# a314-q_d-vcf.net
KiCad netlist of a schematic drawn in EAGLE
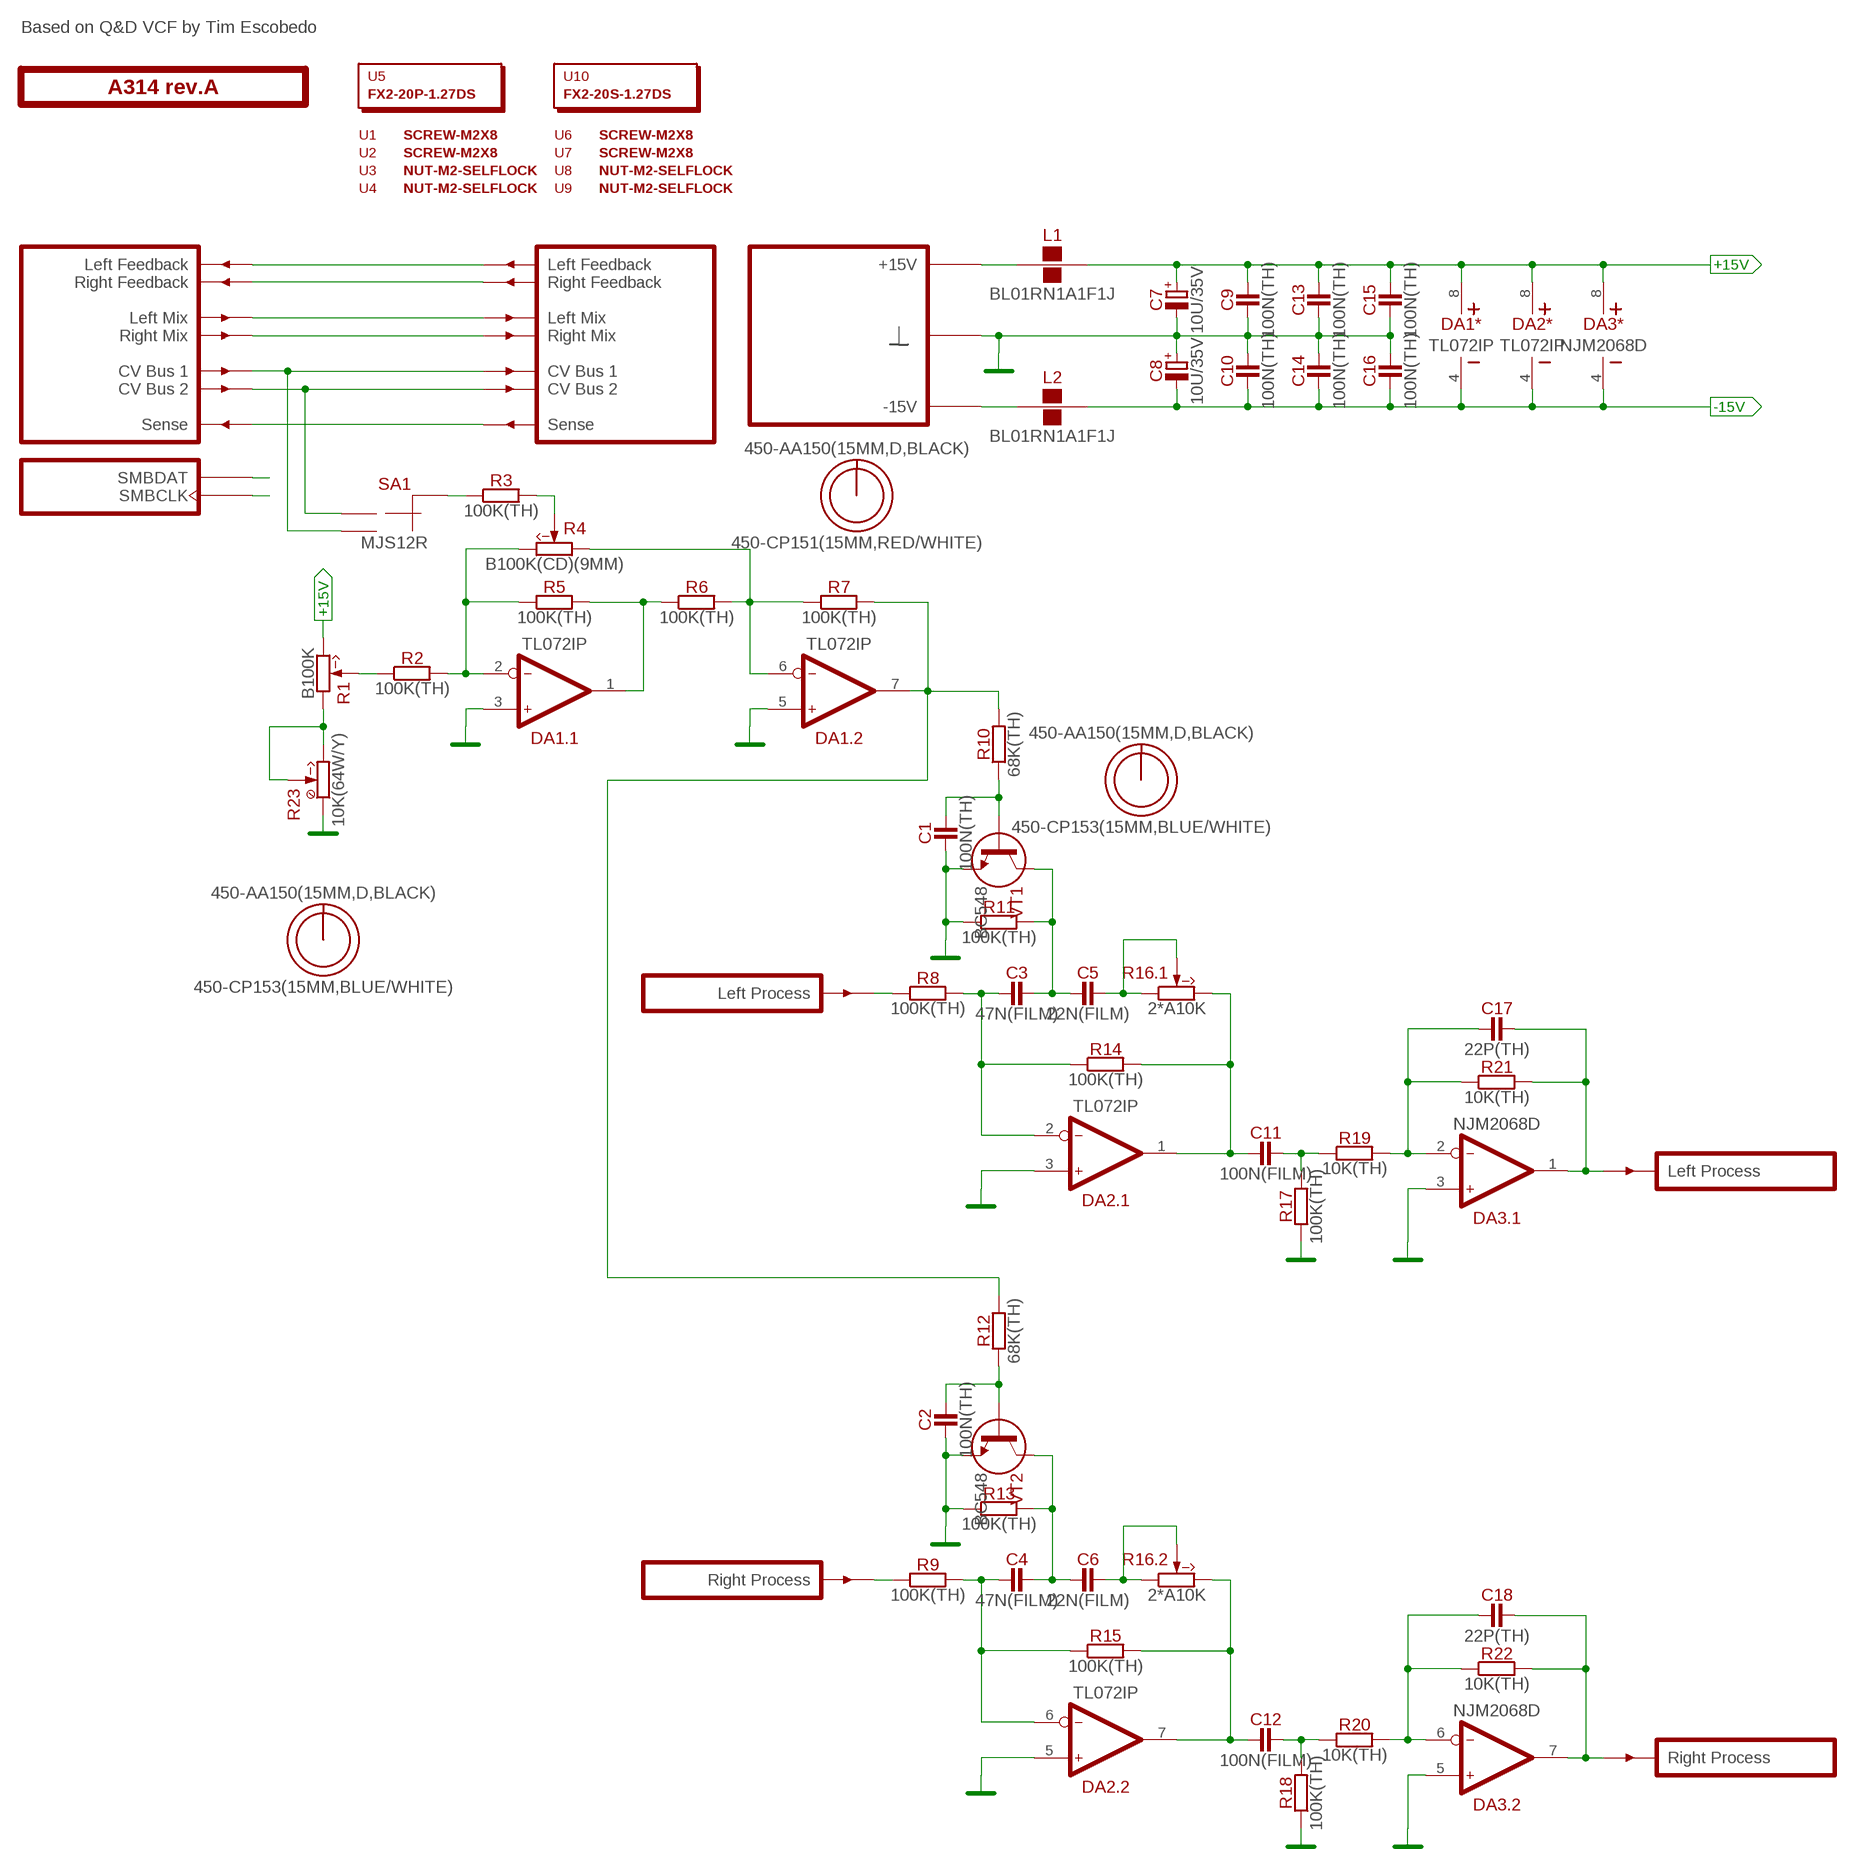
[diagram p0: schematic, sheet 1]

(export (version "E")
  (design (tool "Eeschema 10.0.6"))
  (components
    (comp (ref "C1")
      (value "100N(TH)")
      (footprint "eagle-import:C050-024X044")
      (libsource (lib "eagle-import") (part "?100N(TH)"))
    )
    (comp (ref "C2")
      (value "100N(TH)")
      (footprint "eagle-import:C050-024X044")
      (libsource (lib "eagle-import") (part "?100N(TH)"))
    )
    (comp (ref "C3")
      (value "47N(FILM)")
      (footprint "eagle-import:C050-025X075")
      (libsource (lib "eagle-import") (part "?47N(FILM)"))
    )
    (comp (ref "C4")
      (value "47N(FILM)")
      (footprint "eagle-import:C050-025X075")
      (libsource (lib "eagle-import") (part "?47N(FILM)"))
    )
    (comp (ref "C5")
      (value "22N(FILM)")
      (footprint "eagle-import:C050-025X075")
      (libsource (lib "eagle-import") (part "?22N(FILM)"))
    )
    (comp (ref "C6")
      (value "22N(FILM)")
      (footprint "eagle-import:C050-025X075")
      (libsource (lib "eagle-import") (part "?22N(FILM)"))
    )
    (comp (ref "C7")
      (value "10U/35V")
      (footprint "eagle-import:E2-5")
      (libsource (lib "eagle-import") (part "?10U/35V"))
    )
    (comp (ref "C8")
      (value "10U/35V")
      (footprint "eagle-import:E2-5")
      (libsource (lib "eagle-import") (part "?10U/35V"))
    )
    (comp (ref "C9")
      (value "100N(TH)")
      (footprint "eagle-import:C050-024X044")
      (libsource (lib "eagle-import") (part "?100N(TH)"))
    )
    (comp (ref "C10")
      (value "100N(TH)")
      (footprint "eagle-import:C050-024X044")
      (libsource (lib "eagle-import") (part "?100N(TH)"))
    )
    (comp (ref "C11")
      (value "100N(FILM)")
      (footprint "eagle-import:C050-025X075")
      (libsource (lib "eagle-import") (part "?100N(FILM)"))
    )
    (comp (ref "C12")
      (value "100N(FILM)")
      (footprint "eagle-import:C050-025X075")
      (libsource (lib "eagle-import") (part "?100N(FILM)"))
    )
    (comp (ref "C13")
      (value "100N(TH)")
      (footprint "eagle-import:C050-024X044")
      (libsource (lib "eagle-import") (part "?100N(TH)"))
    )
    (comp (ref "C14")
      (value "100N(TH)")
      (footprint "eagle-import:C050-024X044")
      (libsource (lib "eagle-import") (part "?100N(TH)"))
    )
    (comp (ref "C15")
      (value "100N(TH)")
      (footprint "eagle-import:C050-024X044")
      (libsource (lib "eagle-import") (part "?100N(TH)"))
    )
    (comp (ref "C16")
      (value "100N(TH)")
      (footprint "eagle-import:C050-024X044")
      (libsource (lib "eagle-import") (part "?100N(TH)"))
    )
    (comp (ref "C17")
      (value "22P(TH)")
      (footprint "eagle-import:C050-024X044")
      (libsource (lib "eagle-import") (part "?22P(TH)"))
    )
    (comp (ref "C18")
      (value "22P(TH)")
      (footprint "eagle-import:C050-024X044")
      (libsource (lib "eagle-import") (part "?22P(TH)"))
    )
    (comp (ref "DA1")
      (value "TL072IP")
      (footprint "eagle-import:DIP-8")
      (libsource (lib "eagle-import") (part "TL072IP"))
    )
    (comp (ref "DA2")
      (value "TL072IP")
      (footprint "eagle-import:DIP-8")
      (libsource (lib "eagle-import") (part "TL072IP"))
    )
    (comp (ref "DA3")
      (value "NJM2068D")
      (footprint "eagle-import:DIP-8")
      (libsource (lib "eagle-import") (part "NJM2068D"))
    )
    (comp (ref "L1")
      (value "BL01RN1A1F1J")
      (footprint "eagle-import:BL01RN1A")
      (libsource (lib "eagle-import") (part "BL01RN1A?1F1J"))
    )
    (comp (ref "L2")
      (value "BL01RN1A1F1J")
      (footprint "eagle-import:BL01RN1A")
      (libsource (lib "eagle-import") (part "BL01RN1A?1F1J"))
    )
    (comp (ref "O1")
      (value "450-AA150(15MM,D,BLACK)")
      (footprint "eagle-import:EMPTY")
      (libsource (lib "eagle-import") (part "450-AA?150(15MM,D,BLACK)"))
    )
    (comp (ref "O2")
      (value "450-AA150(15MM,D,BLACK)")
      (footprint "eagle-import:EMPTY")
      (libsource (lib "eagle-import") (part "450-AA?150(15MM,D,BLACK)"))
    )
    (comp (ref "O3")
      (value "450-AA150(15MM,D,BLACK)")
      (footprint "eagle-import:EMPTY")
      (libsource (lib "eagle-import") (part "450-AA?150(15MM,D,BLACK)"))
    )
    (comp (ref "O4")
      (value "450-CP151(15MM,RED/WHITE)")
      (footprint "eagle-import:EMPTY")
      (libsource (lib "eagle-import") (part "450-C?P151(15MM,RED/WHITE)"))
    )
    (comp (ref "O5")
      (value "450-CP153(15MM,BLUE/WHITE)")
      (footprint "eagle-import:EMPTY")
      (libsource (lib "eagle-import") (part "450-C?P153(15MM,BLUE/WHITE)"))
    )
    (comp (ref "O6")
      (value "450-CP153(15MM,BLUE/WHITE)")
      (footprint "eagle-import:EMPTY")
      (libsource (lib "eagle-import") (part "450-C?P153(15MM,BLUE/WHITE)"))
    )
    (comp (ref "PCB1")
      (value "A314 rev.A")
      (footprint "eagle-import:ST2-BOARD-50")
      (libsource (lib "eagle-import") (part "ST2-BOARD-?50"))
    )
    (comp (ref "R1")
      (value "B100K")
      (footprint "eagle-import:RV11-SINGLE")
      (libsource (lib "eagle-import") (part "?B100K"))
    )
    (comp (ref "R2")
      (value "100K(TH)")
      (footprint "eagle-import:R-0207_10")
      (libsource (lib "eagle-import") (part "?100K(TH)"))
    )
    (comp (ref "R3")
      (value "100K(TH)")
      (footprint "eagle-import:R-0207_10")
      (libsource (lib "eagle-import") (part "?100K(TH)"))
    )
    (comp (ref "R4")
      (value "B100K(CD)(9MM)")
      (footprint "eagle-import:RV09-SINGLE")
      (libsource (lib "eagle-import") (part "?B100K(CD)(9MM)"))
    )
    (comp (ref "R5")
      (value "100K(TH)")
      (footprint "eagle-import:R-0207_10")
      (libsource (lib "eagle-import") (part "?100K(TH)"))
    )
    (comp (ref "R6")
      (value "100K(TH)")
      (footprint "eagle-import:R-0207_10")
      (libsource (lib "eagle-import") (part "?100K(TH)"))
    )
    (comp (ref "R7")
      (value "100K(TH)")
      (footprint "eagle-import:R-0207_10")
      (libsource (lib "eagle-import") (part "?100K(TH)"))
    )
    (comp (ref "R8")
      (value "100K(TH)")
      (footprint "eagle-import:R-0207_10")
      (libsource (lib "eagle-import") (part "?100K(TH)"))
    )
    (comp (ref "R9")
      (value "100K(TH)")
      (footprint "eagle-import:R-0207_10")
      (libsource (lib "eagle-import") (part "?100K(TH)"))
    )
    (comp (ref "R10")
      (value "68K(TH)")
      (footprint "eagle-import:R-0207_10")
      (libsource (lib "eagle-import") (part "?68K(TH)"))
    )
    (comp (ref "R11")
      (value "100K(TH)")
      (footprint "eagle-import:R-0207_10")
      (libsource (lib "eagle-import") (part "?100K(TH)"))
    )
    (comp (ref "R12")
      (value "68K(TH)")
      (footprint "eagle-import:R-0207_10")
      (libsource (lib "eagle-import") (part "?68K(TH)"))
    )
    (comp (ref "R13")
      (value "100K(TH)")
      (footprint "eagle-import:R-0207_10")
      (libsource (lib "eagle-import") (part "?100K(TH)"))
    )
    (comp (ref "R14")
      (value "100K(TH)")
      (footprint "eagle-import:R-0207_10")
      (libsource (lib "eagle-import") (part "?100K(TH)"))
    )
    (comp (ref "R15")
      (value "100K(TH)")
      (footprint "eagle-import:R-0207_10")
      (libsource (lib "eagle-import") (part "?100K(TH)"))
    )
    (comp (ref "R16")
      (value "2*A10K")
      (footprint "eagle-import:RV11-DUAL")
      (libsource (lib "eagle-import") (part "2?A10K"))
    )
    (comp (ref "R17")
      (value "100K(TH)")
      (footprint "eagle-import:R-0207_10")
      (libsource (lib "eagle-import") (part "?100K(TH)"))
    )
    (comp (ref "R18")
      (value "100K(TH)")
      (footprint "eagle-import:R-0207_10")
      (libsource (lib "eagle-import") (part "?100K(TH)"))
    )
    (comp (ref "R19")
      (value "10K(TH)")
      (footprint "eagle-import:R-0207_10")
      (libsource (lib "eagle-import") (part "?10K(TH)"))
    )
    (comp (ref "R20")
      (value "10K(TH)")
      (footprint "eagle-import:R-0207_10")
      (libsource (lib "eagle-import") (part "?10K(TH)"))
    )
    (comp (ref "R21")
      (value "10K(TH)")
      (footprint "eagle-import:R-0207_10")
      (libsource (lib "eagle-import") (part "?10K(TH)"))
    )
    (comp (ref "R22")
      (value "10K(TH)")
      (footprint "eagle-import:R-0207_10")
      (libsource (lib "eagle-import") (part "?10K(TH)"))
    )
    (comp (ref "R23")
      (value "10K(64W/Y)")
      (footprint "eagle-import:64W")
      (libsource (lib "eagle-import") (part "?(64W/Y)10K"))
    )
    (comp (ref "SA1")
      (value "MJS12R")
      (footprint "eagle-import:APEM-MJS12R")
      (libsource (lib "eagle-import") (part "MJS12R"))
    )
    (comp (ref "U1")
      (value "SCREW-M2X8")
      (footprint "eagle-import:EMPTY")
      (libsource (lib "eagle-import") (part "?SCREW-M2X8"))
    )
    (comp (ref "U2")
      (value "SCREW-M2X8")
      (footprint "eagle-import:EMPTY")
      (libsource (lib "eagle-import") (part "?SCREW-M2X8"))
    )
    (comp (ref "U3")
      (value "NUT-M2-SELFLOCK")
      (footprint "eagle-import:EMPTY")
      (libsource (lib "eagle-import") (part "?NUT-M2-SELFLOCK"))
    )
    (comp (ref "U4")
      (value "NUT-M2-SELFLOCK")
      (footprint "eagle-import:EMPTY")
      (libsource (lib "eagle-import") (part "?NUT-M2-SELFLOCK"))
    )
    (comp (ref "U5")
      (value "FX2-20P-1.27DS")
      (footprint "eagle-import:EMPTY")
      (libsource (lib "eagle-import") (part "?FX2-20P-1.27DS"))
    )
    (comp (ref "U6")
      (value "SCREW-M2X8")
      (footprint "eagle-import:EMPTY")
      (libsource (lib "eagle-import") (part "?SCREW-M2X8"))
    )
    (comp (ref "U7")
      (value "SCREW-M2X8")
      (footprint "eagle-import:EMPTY")
      (libsource (lib "eagle-import") (part "?SCREW-M2X8"))
    )
    (comp (ref "U8")
      (value "NUT-M2-SELFLOCK")
      (footprint "eagle-import:EMPTY")
      (libsource (lib "eagle-import") (part "?NUT-M2-SELFLOCK"))
    )
    (comp (ref "U9")
      (value "NUT-M2-SELFLOCK")
      (footprint "eagle-import:EMPTY")
      (libsource (lib "eagle-import") (part "?NUT-M2-SELFLOCK"))
    )
    (comp (ref "U10")
      (value "FX2-20S-1.27DS")
      (footprint "eagle-import:EMPTY")
      (libsource (lib "eagle-import") (part "?FX2-20S-1.27DS"))
    )
    (comp (ref "VT1")
      (value "BC548")
      (footprint "eagle-import:TO92")
      (libsource (lib "eagle-import") (part "?BC548"))
    )
    (comp (ref "VT2")
      (value "BC548")
      (footprint "eagle-import:TO92")
      (libsource (lib "eagle-import") (part "?BC548"))
    )
  )
  (nets
    (net (code "1") (name "+15V") (class "Default")
      (node (ref "C13") (pin "2") (pinfunction "2_2") (pintype "passive"))
      (node (ref "C15") (pin "2") (pinfunction "2_2") (pintype "passive"))
      (node (ref "C7") (pin "+") (pinfunction "+_+") (pintype "passive"))
      (node (ref "C9") (pin "2") (pinfunction "2_2") (pintype "passive"))
      (node (ref "DA1") (pin "8") (pinfunction "V+_8") (pintype "power_in"))
      (node (ref "DA2") (pin "8") (pinfunction "V+_8") (pintype "power_in"))
      (node (ref "DA3") (pin "8") (pinfunction "V+_8") (pintype "power_in"))
      (node (ref "L1") (pin "2") (pinfunction "2_2") (pintype "passive"))
      (node (ref "R1") (pin "3") (pinfunction "CW_3") (pintype "passive"))
    )
    (net (code "2") (name "-15V") (class "Default")
      (node (ref "C10") (pin "1") (pinfunction "1_1") (pintype "passive"))
      (node (ref "C14") (pin "1") (pinfunction "1_1") (pintype "passive"))
      (node (ref "C16") (pin "1") (pinfunction "1_1") (pintype "passive"))
      (node (ref "C8") (pin "-") (pinfunction "-_-") (pintype "passive"))
      (node (ref "DA1") (pin "4") (pinfunction "V-_4") (pintype "power_in"))
      (node (ref "DA2") (pin "4") (pinfunction "V-_4") (pintype "power_in"))
      (node (ref "DA3") (pin "4") (pinfunction "V-_4") (pintype "power_in"))
      (node (ref "L2") (pin "2") (pinfunction "2_2") (pintype "passive"))
    )
    (net (code "3") (name "GND") (class "Default")
      (node (ref "C1") (pin "1") (pinfunction "1_1") (pintype "passive"))
      (node (ref "C10") (pin "2") (pinfunction "2_2") (pintype "passive"))
      (node (ref "C13") (pin "1") (pinfunction "1_1") (pintype "passive"))
      (node (ref "C14") (pin "2") (pinfunction "2_2") (pintype "passive"))
      (node (ref "C15") (pin "1") (pinfunction "1_1") (pintype "passive"))
      (node (ref "C16") (pin "2") (pinfunction "2_2") (pintype "passive"))
      (node (ref "C2") (pin "1") (pinfunction "1_1") (pintype "passive"))
      (node (ref "C7") (pin "-") (pinfunction "-_-") (pintype "passive"))
      (node (ref "C8") (pin "+") (pinfunction "+_+") (pintype "passive"))
      (node (ref "C9") (pin "1") (pinfunction "1_1") (pintype "passive"))
      (node (ref "DA1") (pin "3") (pinfunction "IN+_3") (pintype "input"))
      (node (ref "DA1") (pin "5") (pinfunction "IN+_5") (pintype "input"))
      (node (ref "DA2") (pin "3") (pinfunction "IN+_3") (pintype "input"))
      (node (ref "DA2") (pin "5") (pinfunction "IN+_5") (pintype "input"))
      (node (ref "DA3") (pin "3") (pinfunction "IN+_3") (pintype "input"))
      (node (ref "DA3") (pin "5") (pinfunction "IN+_5") (pintype "input"))
      (node (ref "PCB1") (pin "B4") (pinfunction "GND_B4") (pintype "bidirectional"))
      (node (ref "PCB1") (pin "B4'") (pinfunction "GND_B4'") (pintype "bidirectional"))
      (node (ref "PCB1") (pin "B5") (pinfunction "GND_B5") (pintype "bidirectional"))
      (node (ref "PCB1") (pin "B5'") (pinfunction "GND_B5'") (pintype "bidirectional"))
      (node (ref "PCB1") (pin "B6") (pinfunction "GND_B6") (pintype "bidirectional"))
      (node (ref "PCB1") (pin "B6'") (pinfunction "GND_B6'") (pintype "bidirectional"))
      (node (ref "PCB1") (pin "B7") (pinfunction "GND_B7") (pintype "bidirectional"))
      (node (ref "PCB1") (pin "B7'") (pinfunction "GND_B7'") (pintype "bidirectional"))
      (node (ref "PCB1") (pin "B8") (pinfunction "GND_B8") (pintype "bidirectional"))
      (node (ref "PCB1") (pin "B8'") (pinfunction "GND_B8'") (pintype "bidirectional"))
      (node (ref "R11") (pin "1") (pinfunction "1_1") (pintype "passive"))
      (node (ref "R13") (pin "1") (pinfunction "1_1") (pintype "passive"))
      (node (ref "R17") (pin "1") (pinfunction "1_1") (pintype "passive"))
      (node (ref "R18") (pin "1") (pinfunction "1_1") (pintype "passive"))
      (node (ref "R23") (pin "1") (pinfunction "CCW_1") (pintype "passive"))
      (node (ref "VT1") (pin "3") (pinfunction "E_3") (pintype "passive"))
      (node (ref "VT2") (pin "3") (pinfunction "E_3") (pintype "passive"))
    )
    (net (code "4") (name "Net-(C11-Pad2)") (class "Default")
      (node (ref "C11") (pin "2") (pinfunction "2_2") (pintype "passive"))
      (node (ref "R17") (pin "2") (pinfunction "2_2") (pintype "passive"))
      (node (ref "R19") (pin "1") (pinfunction "1_1") (pintype "passive"))
    )
    (net (code "5") (name "Net-(C12-Pad2)") (class "Default")
      (node (ref "C12") (pin "2") (pinfunction "2_2") (pintype "passive"))
      (node (ref "R18") (pin "2") (pinfunction "2_2") (pintype "passive"))
      (node (ref "R20") (pin "1") (pinfunction "1_1") (pintype "passive"))
    )
    (net (code "6") (name "Net-(DA1B-IN-)") (class "Default")
      (node (ref "DA1") (pin "2") (pinfunction "IN-_2") (pintype "input"))
      (node (ref "R2") (pin "2") (pinfunction "2_2") (pintype "passive"))
      (node (ref "R4") (pin "3") (pinfunction "CW_3") (pintype "passive"))
      (node (ref "R5") (pin "1") (pinfunction "1_1") (pintype "passive"))
    )
    (net (code "7") (name "Net-(DA1B-OUT)") (class "Default")
      (node (ref "DA1") (pin "1") (pinfunction "OUT_1") (pintype "output"))
      (node (ref "R5") (pin "2") (pinfunction "2_2") (pintype "passive"))
      (node (ref "R6") (pin "1") (pinfunction "1_1") (pintype "passive"))
    )
    (net (code "8") (name "Net-(DA1C-IN-)") (class "Default")
      (node (ref "DA1") (pin "6") (pinfunction "IN-_6") (pintype "input"))
      (node (ref "R4") (pin "1") (pinfunction "CCW_1") (pintype "passive"))
      (node (ref "R6") (pin "2") (pinfunction "2_2") (pintype "passive"))
      (node (ref "R7") (pin "1") (pinfunction "1_1") (pintype "passive"))
    )
    (net (code "9") (name "Net-(DA1C-OUT)") (class "Default")
      (node (ref "DA1") (pin "7") (pinfunction "OUT_7") (pintype "output"))
      (node (ref "R10") (pin "2") (pinfunction "2_2") (pintype "passive"))
      (node (ref "R12") (pin "2") (pinfunction "2_2") (pintype "passive"))
      (node (ref "R7") (pin "2") (pinfunction "2_2") (pintype "passive"))
    )
    (net (code "10") (name "Net-(DA2B-IN-)") (class "Default")
      (node (ref "C3") (pin "1") (pinfunction "1_1") (pintype "passive"))
      (node (ref "DA2") (pin "2") (pinfunction "IN-_2") (pintype "input"))
      (node (ref "R14") (pin "1") (pinfunction "1_1") (pintype "passive"))
      (node (ref "R8") (pin "2") (pinfunction "2_2") (pintype "passive"))
    )
    (net (code "11") (name "Net-(DA2B-OUT)") (class "Default")
      (node (ref "C11") (pin "1") (pinfunction "1_1") (pintype "passive"))
      (node (ref "DA2") (pin "1") (pinfunction "OUT_1") (pintype "output"))
      (node (ref "R14") (pin "2") (pinfunction "2_2") (pintype "passive"))
      (node (ref "R16") (pin "3") (pinfunction "CW_3") (pintype "passive"))
    )
    (net (code "12") (name "Net-(DA2C-IN-)") (class "Default")
      (node (ref "C4") (pin "1") (pinfunction "1_1") (pintype "passive"))
      (node (ref "DA2") (pin "6") (pinfunction "IN-_6") (pintype "input"))
      (node (ref "R15") (pin "1") (pinfunction "1_1") (pintype "passive"))
      (node (ref "R9") (pin "2") (pinfunction "2_2") (pintype "passive"))
    )
    (net (code "13") (name "Net-(DA2C-OUT)") (class "Default")
      (node (ref "C12") (pin "1") (pinfunction "1_1") (pintype "passive"))
      (node (ref "DA2") (pin "7") (pinfunction "OUT_7") (pintype "output"))
      (node (ref "R15") (pin "2") (pinfunction "2_2") (pintype "passive"))
      (node (ref "R16") (pin "3'") (pinfunction "CW_3'") (pintype "passive"))
    )
    (net (code "14") (name "Net-(DA3B-IN-)") (class "Default")
      (node (ref "C17") (pin "1") (pinfunction "1_1") (pintype "passive"))
      (node (ref "DA3") (pin "2") (pinfunction "IN-_2") (pintype "input"))
      (node (ref "R19") (pin "2") (pinfunction "2_2") (pintype "passive"))
      (node (ref "R21") (pin "1") (pinfunction "1_1") (pintype "passive"))
    )
    (net (code "15") (name "Net-(DA3B-OUT)") (class "Default")
      (node (ref "C17") (pin "2") (pinfunction "2_2") (pintype "passive"))
      (node (ref "DA3") (pin "1") (pinfunction "OUT_1") (pintype "output"))
      (node (ref "PCB1") (pin "BOUTL'") (pinfunction "OUTL_BOUTL'") (pintype "bidirectional"))
      (node (ref "R21") (pin "2") (pinfunction "2_2") (pintype "passive"))
    )
    (net (code "16") (name "Net-(DA3C-IN-)") (class "Default")
      (node (ref "C18") (pin "1") (pinfunction "1_1") (pintype "passive"))
      (node (ref "DA3") (pin "6") (pinfunction "IN-_6") (pintype "input"))
      (node (ref "R20") (pin "2") (pinfunction "2_2") (pintype "passive"))
      (node (ref "R22") (pin "1") (pinfunction "1_1") (pintype "passive"))
    )
    (net (code "17") (name "Net-(DA3C-OUT)") (class "Default")
      (node (ref "C18") (pin "2") (pinfunction "2_2") (pintype "passive"))
      (node (ref "DA3") (pin "7") (pinfunction "OUT_7") (pintype "output"))
      (node (ref "PCB1") (pin "BOUTR'") (pinfunction "OUTR_BOUTR'") (pintype "bidirectional"))
      (node (ref "R22") (pin "2") (pinfunction "2_2") (pintype "passive"))
    )
    (net (code "18") (name "Net-(L1-Pad1)") (class "Default")
      (node (ref "L1") (pin "1") (pinfunction "1_1") (pintype "passive"))
      (node (ref "PCB1") (pin "A+15") (pinfunction "P+15V_A+15") (pintype "bidirectional"))
      (node (ref "PCB1") (pin "A+15'") (pinfunction "P+15V_A+15'") (pintype "bidirectional"))
      (node (ref "PCB1") (pin "B+15") (pinfunction "P+15V_B+15") (pintype "bidirectional"))
      (node (ref "PCB1") (pin "B+15'") (pinfunction "P+15V_B+15'") (pintype "bidirectional"))
    )
    (net (code "19") (name "Net-(L2-Pad1)") (class "Default")
      (node (ref "L2") (pin "1") (pinfunction "1_1") (pintype "passive"))
      (node (ref "PCB1") (pin "A-15") (pinfunction "P-15V_A-15") (pintype "bidirectional"))
      (node (ref "PCB1") (pin "A-15'") (pinfunction "P-15V_A-15'") (pintype "bidirectional"))
      (node (ref "PCB1") (pin "B-15") (pinfunction "P-15V_B-15") (pintype "bidirectional"))
      (node (ref "PCB1") (pin "B-15'") (pinfunction "P-15V_B-15'") (pintype "bidirectional"))
    )
    (net (code "20") (name "Net-(PCB1B-INL)") (class "Default")
      (node (ref "PCB1") (pin "BINL") (pinfunction "INL_BINL") (pintype "bidirectional"))
      (node (ref "R8") (pin "1") (pinfunction "1_1") (pintype "passive"))
    )
    (net (code "21") (name "Net-(PCB1C-INR)") (class "Default")
      (node (ref "PCB1") (pin "BINR") (pinfunction "INR_BINR") (pintype "bidirectional"))
      (node (ref "R9") (pin "1") (pinfunction "1_1") (pintype "passive"))
    )
    (net (code "22") (name "Net-(PCB1F-CV1)") (class "Default")
      (node (ref "PCB1") (pin "ACV1") (pinfunction "CV1_ACV1") (pintype "bidirectional"))
      (node (ref "PCB1") (pin "ACV1'") (pinfunction "CV1'_ACV1'") (pintype "bidirectional"))
      (node (ref "SA1") (pin "NO") (pinfunction "2_NO") (pintype "passive"))
    )
    (net (code "23") (name "Net-(PCB1F-CV2)") (class "Default")
      (node (ref "PCB1") (pin "ACV2") (pinfunction "CV2_ACV2") (pintype "bidirectional"))
      (node (ref "PCB1") (pin "ACV2'") (pinfunction "CV2'_ACV2'") (pintype "bidirectional"))
      (node (ref "SA1") (pin "NC") (pinfunction "1_NC") (pintype "passive"))
    )
    (net (code "24") (name "Net-(PCB1F-LFBK)") (class "Default")
      (node (ref "PCB1") (pin "ALFBK") (pinfunction "LFBK_ALFBK") (pintype "bidirectional"))
      (node (ref "PCB1") (pin "ALFBK'") (pinfunction "LFBK'_ALFBK'") (pintype "bidirectional"))
    )
    (net (code "25") (name "Net-(PCB1F-LMIX)") (class "Default")
      (node (ref "PCB1") (pin "ALMIX") (pinfunction "LMIX_ALMIX") (pintype "bidirectional"))
      (node (ref "PCB1") (pin "ALMIX'") (pinfunction "LMIX'_ALMIX'") (pintype "bidirectional"))
    )
    (net (code "26") (name "Net-(PCB1F-RFBK)") (class "Default")
      (node (ref "PCB1") (pin "ARFBK") (pinfunction "RFBK_ARFBK") (pintype "bidirectional"))
      (node (ref "PCB1") (pin "ARFBK'") (pinfunction "RFBK'_ARFBK'") (pintype "bidirectional"))
    )
    (net (code "27") (name "Net-(PCB1F-RMIX)") (class "Default")
      (node (ref "PCB1") (pin "ARMIX") (pinfunction "RMIX_ARMIX") (pintype "bidirectional"))
      (node (ref "PCB1") (pin "ARMIX'") (pinfunction "RMIX'_ARMIX'") (pintype "bidirectional"))
    )
    (net (code "28") (name "Net-(PCB1F-SENSE)") (class "Default")
      (node (ref "PCB1") (pin "BSENSE") (pinfunction "SENSE_BSENSE") (pintype "bidirectional"))
      (node (ref "PCB1") (pin "BSENSE'") (pinfunction "SENSE'_BSENSE'") (pintype "bidirectional"))
    )
    (net (code "29") (name "Net-(PCB1H-SMBCLK-PadASMBCLK')") (class "Default")
      (node (ref "PCB1") (pin "ASMBCLK") (pinfunction "SMBCLK_ASMBCLK") (pintype "bidirectional"))
      (node (ref "PCB1") (pin "ASMBCLK'") (pinfunction "SMBCLK_ASMBCLK'") (pintype "bidirectional"))
    )
    (net (code "30") (name "Net-(PCB1H-SMBDAT-PadASMBDAT')") (class "Default")
      (node (ref "PCB1") (pin "ASMBDAT") (pinfunction "SMBDAT_ASMBDAT") (pintype "bidirectional"))
      (node (ref "PCB1") (pin "ASMBDAT'") (pinfunction "SMBDAT_ASMBDAT'") (pintype "bidirectional"))
    )
    (net (code "31") (name "Net-(R1-CCW)") (class "Default")
      (node (ref "R1") (pin "1") (pinfunction "CCW_1") (pintype "passive"))
      (node (ref "R23") (pin "3") (pinfunction "CW_3") (pintype "passive"))
      (node (ref "R23") (pin "S") (pinfunction "W_S") (pintype "passive"))
      (node (ref "R23") (pin "S@1") (pinfunction "W_S@1") (pintype "passive"))
    )
    (net (code "32") (name "Net-(R1-W)") (class "Default")
      (node (ref "R1") (pin "2") (pinfunction "W_2") (pintype "passive"))
      (node (ref "R2") (pin "1") (pinfunction "1_1") (pintype "passive"))
    )
    (net (code "33") (name "Net-(R4-W)") (class "Default")
      (node (ref "R3") (pin "2") (pinfunction "2_2") (pintype "passive"))
      (node (ref "R4") (pin "2") (pinfunction "W_2") (pintype "passive"))
    )
    (net (code "34") (name "Net-(R16A-CCW)") (class "Default")
      (node (ref "C5") (pin "2") (pinfunction "2_2") (pintype "passive"))
      (node (ref "R16") (pin "1") (pinfunction "CCW_1") (pintype "passive"))
      (node (ref "R16") (pin "2") (pinfunction "W_2") (pintype "passive"))
    )
    (net (code "35") (name "Net-(R16B-CCW)") (class "Default")
      (node (ref "C6") (pin "2") (pinfunction "2_2") (pintype "passive"))
      (node (ref "R16") (pin "1'") (pinfunction "CCW_1'") (pintype "passive"))
      (node (ref "R16") (pin "2'") (pinfunction "W_2'") (pintype "passive"))
    )
    (net (code "36") (name "Net-(SA1-CM)") (class "Default")
      (node (ref "R3") (pin "1") (pinfunction "1_1") (pintype "passive"))
      (node (ref "SA1") (pin "C") (pinfunction "CM_C") (pintype "passive"))
    )
    (net (code "37") (name "Net-(VT1-B)") (class "Default")
      (node (ref "C1") (pin "2") (pinfunction "2_2") (pintype "passive"))
      (node (ref "R10") (pin "1") (pinfunction "1_1") (pintype "passive"))
      (node (ref "VT1") (pin "2") (pinfunction "B_2") (pintype "passive"))
    )
    (net (code "38") (name "Net-(VT1-C)") (class "Default")
      (node (ref "C3") (pin "2") (pinfunction "2_2") (pintype "passive"))
      (node (ref "C5") (pin "1") (pinfunction "1_1") (pintype "passive"))
      (node (ref "R11") (pin "2") (pinfunction "2_2") (pintype "passive"))
      (node (ref "VT1") (pin "1") (pinfunction "C_1") (pintype "passive"))
    )
    (net (code "39") (name "Net-(VT2-B)") (class "Default")
      (node (ref "C2") (pin "2") (pinfunction "2_2") (pintype "passive"))
      (node (ref "R12") (pin "1") (pinfunction "1_1") (pintype "passive"))
      (node (ref "VT2") (pin "2") (pinfunction "B_2") (pintype "passive"))
    )
    (net (code "40") (name "Net-(VT2-C)") (class "Default")
      (node (ref "C4") (pin "2") (pinfunction "2_2") (pintype "passive"))
      (node (ref "C6") (pin "1") (pinfunction "1_1") (pintype "passive"))
      (node (ref "R13") (pin "2") (pinfunction "2_2") (pintype "passive"))
      (node (ref "VT2") (pin "1") (pinfunction "C_1") (pintype "passive"))
    )
  )
)
